# openSX70_WIP_NEW_LAYOUT_20171230_V30_man.net
KiCad netlist of a schematic drawn in EAGLE
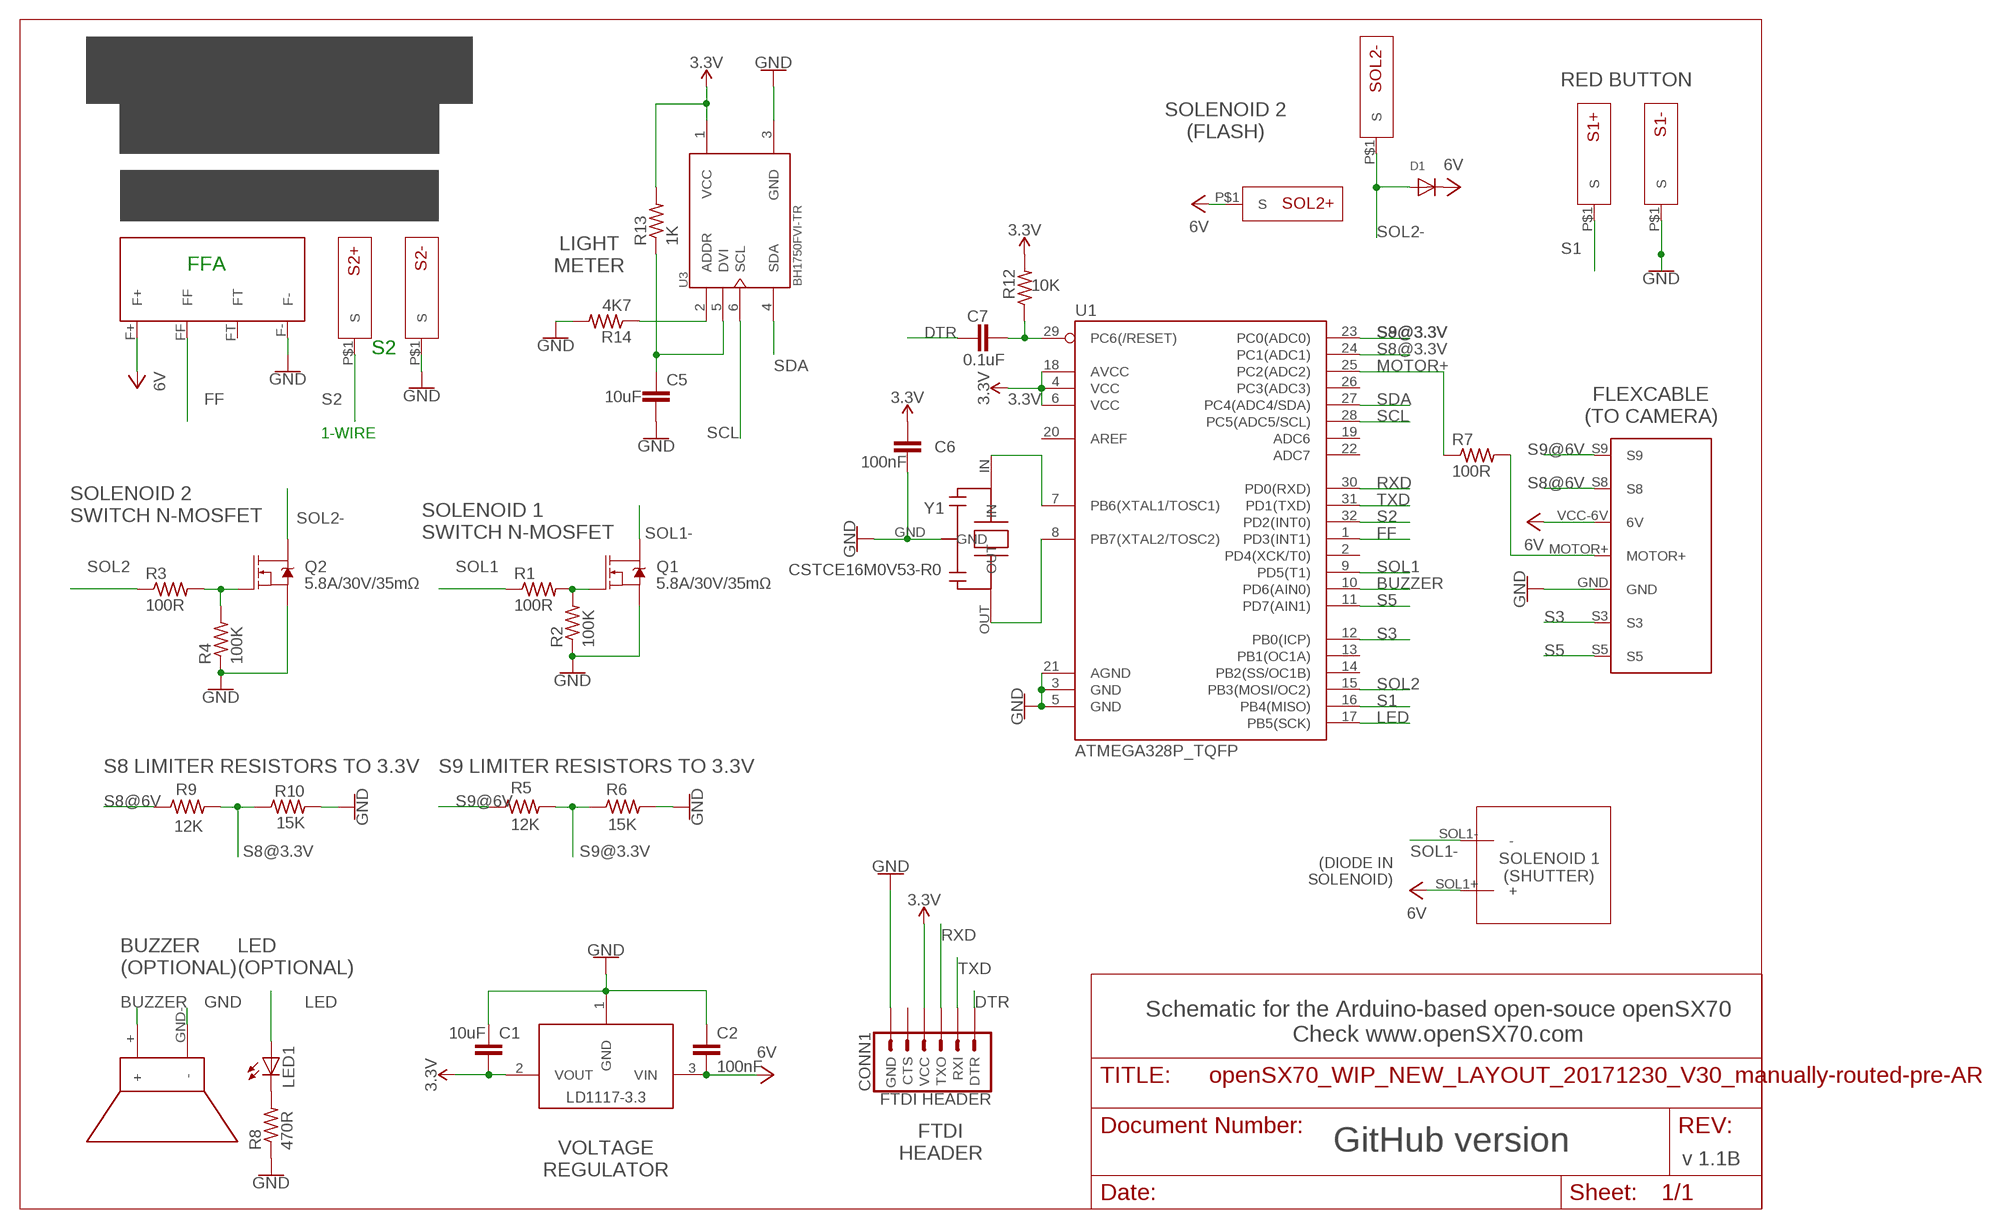
[diagram p0: schematic, sheet 1]

(export (version "E")
  (design (tool "Eeschema 10.0.6"))
  (components
    (comp (ref "BUZZ1")
      (value "CSET8-5G")
      (footprint "eagle-import:CSET8-5G_PACKAGE")
      (libsource (lib "eagle-import") (part "CSET8-5G"))
    )
    (comp (ref "C1")
      (value "10uF")
      (footprint "eagle-import:0603")
      (libsource (lib "eagle-import") (part "10UF-0603-6.3V-20%"))
    )
    (comp (ref "C2")
      (value "100nF")
      (footprint "eagle-import:C0603K")
      (libsource (lib "eagle-import") (part "C-EUC0603K"))
    )
    (comp (ref "C5")
      (value "10uF")
      (footprint "eagle-import:0603")
      (libsource (lib "eagle-import") (part "10UF-0603-6.3V-20%"))
    )
    (comp (ref "C6")
      (value "100nF")
      (footprint "eagle-import:C0805")
      (libsource (lib "eagle-import") (part "resistor_C-EUC0805"))
    )
    (comp (ref "C7")
      (value "0.1uF")
      (footprint "eagle-import:0603")
      (libsource (lib "eagle-import") (part "0.1UF-0603-25V-(+80/-20%)"))
    )
    (comp (ref "CONN1")
      (value "FTDI HEADER")
      (footprint "eagle-import:1X06")
      (libsource (lib "eagle-import") (part "6_PIN_SERIAL_TARGET"))
    )
    (comp (ref "D1")
      (value "DIODESOD-523")
      (footprint "eagle-import:SOD-523")
      (libsource (lib "eagle-import") (part "DIODESOD-523"))
    )
    (comp (ref "LD11173.3V")
      (value "LD1117 3.3V")
      (footprint "eagle-import:SOT223")
      (fields (field (name "MF") "Advanced Monolithic Systems") (field (name "MP") "AMS1117-5.0"))
      (libsource (lib "eagle-import") (part "LD1117-3.3"))
    )
    (comp (ref "LED1")
      (value "LEDCHIPLED_0805")
      (footprint "eagle-import:CHIPLED_0805")
      (libsource (lib "eagle-import") (part "LEDCHIPLED_0805"))
    )
    (comp (ref "Q1")
      (value "5.8A/30V/35mΩ")
      (footprint "eagle-import:SOT23-3")
      (libsource (lib "eagle-import") (part "MOSFET-NCH-AO3404A"))
    )
    (comp (ref "Q2")
      (value "5.8A/30V/35mΩ")
      (footprint "eagle-import:SOT23-3")
      (libsource (lib "eagle-import") (part "MOSFET-NCH-AO3404A"))
    )
    (comp (ref "R1")
      (value "100R")
      (footprint "eagle-import:R0603")
      (libsource (lib "eagle-import") (part "R-US_R0603"))
    )
    (comp (ref "R2")
      (value "100K")
      (footprint "eagle-import:R0603")
      (libsource (lib "eagle-import") (part "R-US_R0603"))
    )
    (comp (ref "R3")
      (value "100R")
      (footprint "eagle-import:R0603")
      (libsource (lib "eagle-import") (part "R-US_R0603"))
    )
    (comp (ref "R4")
      (value "100K")
      (footprint "eagle-import:R0603")
      (libsource (lib "eagle-import") (part "R-US_R0603"))
    )
    (comp (ref "R5")
      (value "12K")
      (footprint "eagle-import:R0603")
      (libsource (lib "eagle-import") (part "R-US_R0603"))
    )
    (comp (ref "R6")
      (value "15K")
      (footprint "eagle-import:R0603")
      (libsource (lib "eagle-import") (part "R-US_R0603"))
    )
    (comp (ref "R7")
      (value "100R")
      (footprint "eagle-import:R0603")
      (libsource (lib "eagle-import") (part "R-US_R0603"))
    )
    (comp (ref "R8")
      (value "470R")
      (footprint "eagle-import:R0603")
      (libsource (lib "eagle-import") (part "R-US_R0603"))
    )
    (comp (ref "R9")
      (value "12K")
      (footprint "eagle-import:R0603")
      (libsource (lib "eagle-import") (part "R-US_R0603"))
    )
    (comp (ref "R10")
      (value "15K")
      (footprint "eagle-import:R0603")
      (libsource (lib "eagle-import") (part "R-US_R0603"))
    )
    (comp (ref "R12")
      (value "10K")
      (footprint "eagle-import:R0603")
      (libsource (lib "eagle-import") (part "R-US_R0603"))
    )
    (comp (ref "R13")
      (value "1K")
      (footprint "eagle-import:R0603")
      (libsource (lib "eagle-import") (part "R-US_R0603"))
    )
    (comp (ref "R14")
      (value "4K7")
      (footprint "eagle-import:R0603")
      (libsource (lib "eagle-import") (part "R-US_R0603"))
    )
    (comp (ref "S1+")
      (value "SX70_S-PAD")
      (footprint "eagle-import:SX70-S-PAD")
      (libsource (lib "eagle-import") (part "SX70_S-PAD"))
    )
    (comp (ref "S1-")
      (value "SX70_S-PAD")
      (footprint "eagle-import:SX70-S-PAD")
      (libsource (lib "eagle-import") (part "SX70_S-PAD"))
    )
    (comp (ref "S2+")
      (value "SX70_S-PAD")
      (footprint "eagle-import:SX70-S-PAD")
      (libsource (lib "eagle-import") (part "SX70_S-PAD"))
    )
    (comp (ref "S2-")
      (value "SX70_S-PAD")
      (footprint "eagle-import:SX70-S-PAD")
      (libsource (lib "eagle-import") (part "SX70_S-PAD"))
    )
    (comp (ref "SOL1")
      (value "SX70-SOLENOID1-2PADS")
      (footprint "eagle-import:SX70-SOLENOID1-2")
      (libsource (lib "eagle-import") (part "SX70-SOLENOID1-2PADS"))
    )
    (comp (ref "SOL2+")
      (value "SX70_S-PAD")
      (footprint "eagle-import:SX70-S-PAD")
      (libsource (lib "eagle-import") (part "SX70_S-PAD"))
    )
    (comp (ref "SOL2-")
      (value "SX70_S-PAD")
      (footprint "eagle-import:SX70-S-PAD")
      (libsource (lib "eagle-import") (part "SX70_S-PAD"))
    )
    (comp (ref "U$1")
      (value "SX70-7-PAD")
      (footprint "eagle-import:SX70-7-PAD")
      (libsource (lib "eagle-import") (part "SX70-7-PAD"))
    )
    (comp (ref "U$2")
      (value "FFA")
      (footprint "eagle-import:FFA-PAD-PACKAGE")
      (libsource (lib "eagle-import") (part "SX70-FFA-PAD"))
    )
    (comp (ref "U1")
      (value "ATMEGA328P_TQFP")
      (footprint "eagle-import:TQFP32-08")
      (libsource (lib "eagle-import") (part "ATMEGA328P_TQFP"))
    )
    (comp (ref "U3")
      (value "BH1750FVI-TR")
      (footprint "eagle-import:SOTFL50P300X75-6N")
      (fields (field (name "MF") "Rohm"))
      (libsource (lib "eagle-import") (part "BH1750FVI-TR"))
    )
    (comp (ref "Y1")
      (value "CSTCE16M0V53-R0")
      (footprint "eagle-import:CFP95P160X100-3N")
      (fields (field (name "MF") "Murata"))
      (libsource (lib "eagle-import") (part "CSTCE16M0V53-R0"))
    )
  )
  (nets
    (net (code "1") (name "/BUZZER") (class "Default")
      (node (ref "BUZZ1") (pin "+") (pinfunction "+_+") (pintype "bidirectional"))
      (node (ref "U1") (pin "10") (pinfunction "PD6(AIN0)_10") (pintype "bidirectional"))
    )
    (net (code "2") (name "/DTR") (class "Default")
      (node (ref "C7") (pin "1") (pinfunction "1_1") (pintype "passive"))
      (node (ref "CONN1") (pin "1") (pinfunction "DTR_1") (pintype "passive"))
    )
    (net (code "3") (name "/FF") (class "Default")
      (node (ref "U$2") (pin "FF") (pinfunction "FF_FF") (pintype "bidirectional"))
      (node (ref "U1") (pin "1") (pinfunction "PD3(INT1)_1") (pintype "bidirectional"))
    )
    (net (code "4") (name "/LED") (class "Default")
      (node (ref "LED1") (pin "A") (pinfunction "A_A") (pintype "passive"))
      (node (ref "U1") (pin "17") (pinfunction "PB5(SCK)_17") (pintype "bidirectional"))
    )
    (net (code "5") (name "/MOTOR+") (class "Default")
      (node (ref "R7") (pin "1") (pinfunction "1_1") (pintype "passive"))
      (node (ref "U1") (pin "25") (pinfunction "PC2(ADC2)_25") (pintype "bidirectional"))
    )
    (net (code "6") (name "/RXD") (class "Default")
      (node (ref "CONN1") (pin "3") (pinfunction "TXO_3") (pintype "passive"))
      (node (ref "U1") (pin "30") (pinfunction "PD0(RXD)_30") (pintype "bidirectional"))
    )
    (net (code "7") (name "/S1") (class "Default")
      (node (ref "S1+") (pin "P$1") (pinfunction "S_P$1") (pintype "bidirectional"))
      (node (ref "U1") (pin "16") (pinfunction "PB4(MISO)_16") (pintype "bidirectional"))
    )
    (net (code "8") (name "/S2") (class "Default")
      (node (ref "S2+") (pin "P$1") (pinfunction "S_P$1") (pintype "bidirectional"))
      (node (ref "U1") (pin "32") (pinfunction "PD2(INT0)_32") (pintype "bidirectional"))
    )
    (net (code "9") (name "/S3") (class "Default")
      (node (ref "U$1") (pin "S3") (pinfunction "S3_S3") (pintype "bidirectional"))
      (node (ref "U1") (pin "12") (pinfunction "PB0(ICP)_12") (pintype "bidirectional"))
    )
    (net (code "10") (name "/S5") (class "Default")
      (node (ref "U$1") (pin "S5") (pinfunction "S5_S5") (pintype "bidirectional"))
      (node (ref "U1") (pin "11") (pinfunction "PD7(AIN1)_11") (pintype "bidirectional"))
    )
    (net (code "11") (name "/S8@3.3V") (class "Default")
      (node (ref "R10") (pin "1") (pinfunction "1_1") (pintype "passive"))
      (node (ref "R9") (pin "2") (pinfunction "2_2") (pintype "passive"))
      (node (ref "U1") (pin "24") (pinfunction "PC1(ADC1)_24") (pintype "bidirectional"))
    )
    (net (code "12") (name "/S8@6V") (class "Default")
      (node (ref "R9") (pin "1") (pinfunction "1_1") (pintype "passive"))
      (node (ref "U$1") (pin "S8") (pinfunction "S8_S8") (pintype "bidirectional"))
    )
    (net (code "13") (name "/S9@3.3V") (class "Default")
      (node (ref "R5") (pin "2") (pinfunction "2_2") (pintype "passive"))
      (node (ref "R6") (pin "1") (pinfunction "1_1") (pintype "passive"))
      (node (ref "U1") (pin "23") (pinfunction "PC0(ADC0)_23") (pintype "bidirectional"))
    )
    (net (code "14") (name "/S9@6V") (class "Default")
      (node (ref "R5") (pin "1") (pinfunction "1_1") (pintype "passive"))
      (node (ref "U$1") (pin "S9") (pinfunction "S9_S9") (pintype "bidirectional"))
    )
    (net (code "15") (name "/SCL") (class "Default")
      (node (ref "U1") (pin "28") (pinfunction "PC5(ADC5/SCL)_28") (pintype "bidirectional"))
      (node (ref "U3") (pin "6") (pinfunction "SCL_6") (pintype "input"))
    )
    (net (code "16") (name "/SDA") (class "Default")
      (node (ref "U1") (pin "27") (pinfunction "PC4(ADC4/SDA)_27") (pintype "bidirectional"))
      (node (ref "U3") (pin "4") (pinfunction "SDA_4") (pintype "bidirectional"))
    )
    (net (code "17") (name "/SOL1") (class "Default")
      (node (ref "R1") (pin "1") (pinfunction "1_1") (pintype "passive"))
      (node (ref "U1") (pin "9") (pinfunction "PD5(T1)_9") (pintype "bidirectional"))
    )
    (net (code "18") (name "/SOL1-") (class "Default")
      (node (ref "Q1") (pin "3") (pinfunction "D_3") (pintype "bidirectional"))
      (node (ref "SOL1") (pin "SOL1-") (pinfunction "-_SOL1-") (pintype "bidirectional"))
    )
    (net (code "19") (name "/SOL2") (class "Default")
      (node (ref "R3") (pin "1") (pinfunction "1_1") (pintype "passive"))
      (node (ref "U1") (pin "15") (pinfunction "PB3(MOSI/OC2)_15") (pintype "bidirectional"))
    )
    (net (code "20") (name "/SOL2-") (class "Default")
      (node (ref "D1") (pin "A") (pinfunction "A_A") (pintype "passive"))
      (node (ref "Q2") (pin "3") (pinfunction "D_3") (pintype "bidirectional"))
      (node (ref "SOL2-") (pin "P$1") (pinfunction "S_P$1") (pintype "bidirectional"))
    )
    (net (code "21") (name "/TXD") (class "Default")
      (node (ref "CONN1") (pin "2") (pinfunction "RXI_2") (pintype "passive"))
      (node (ref "U1") (pin "31") (pinfunction "PD1(TXD)_31") (pintype "bidirectional"))
    )
    (net (code "22") (name "3.3V") (class "Default")
      (node (ref "C1") (pin "2") (pinfunction "2_2") (pintype "passive"))
      (node (ref "C6") (pin "1") (pinfunction "1_1") (pintype "passive"))
      (node (ref "CONN1") (pin "4") (pinfunction "VCC_4") (pintype "passive"))
      (node (ref "LD11173.3V") (pin "2") (pinfunction "VOUT_2") (pintype "bidirectional"))
      (node (ref "R12") (pin "2") (pinfunction "2_2") (pintype "passive"))
      (node (ref "R13") (pin "2") (pinfunction "2_2") (pintype "passive"))
      (node (ref "U1") (pin "18") (pinfunction "AVCC_18") (pintype "bidirectional"))
      (node (ref "U1") (pin "4") (pinfunction "VCC_4") (pintype "bidirectional"))
      (node (ref "U1") (pin "6") (pinfunction "VCC_6") (pintype "bidirectional"))
      (node (ref "U3") (pin "1") (pinfunction "VCC_1") (pintype "power_in"))
    )
    (net (code "23") (name "6V") (class "Default")
      (node (ref "C2") (pin "2") (pinfunction "2_2") (pintype "passive"))
      (node (ref "D1") (pin "K") (pinfunction "C_K") (pintype "passive"))
      (node (ref "LD11173.3V") (pin "3") (pinfunction "VIN_3") (pintype "bidirectional"))
      (node (ref "SOL1") (pin "SOL1+") (pinfunction "+_SOL1+") (pintype "bidirectional"))
      (node (ref "SOL2+") (pin "P$1") (pinfunction "S_P$1") (pintype "bidirectional"))
      (node (ref "U$1") (pin "VCC-6V") (pinfunction "6V_VCC-6V") (pintype "bidirectional"))
      (node (ref "U$2") (pin "F+") (pinfunction "F+_F+") (pintype "bidirectional"))
    )
    (net (code "24") (name "GND") (class "Default")
      (node (ref "BUZZ1") (pin "GND-") (pinfunction "-_GND-") (pintype "bidirectional"))
      (node (ref "C1") (pin "1") (pinfunction "1_1") (pintype "passive"))
      (node (ref "C2") (pin "1") (pinfunction "1_1") (pintype "passive"))
      (node (ref "C5") (pin "2") (pinfunction "2_2") (pintype "passive"))
      (node (ref "C6") (pin "2") (pinfunction "2_2") (pintype "passive"))
      (node (ref "CONN1") (pin "6") (pinfunction "GND_6") (pintype "passive"))
      (node (ref "LD11173.3V") (pin "1") (pinfunction "GND_1") (pintype "bidirectional"))
      (node (ref "Q1") (pin "2") (pinfunction "S_2") (pintype "bidirectional"))
      (node (ref "Q2") (pin "2") (pinfunction "S_2") (pintype "bidirectional"))
      (node (ref "R10") (pin "2") (pinfunction "2_2") (pintype "passive"))
      (node (ref "R14") (pin "2") (pinfunction "2_2") (pintype "passive"))
      (node (ref "R2") (pin "1") (pinfunction "1_1") (pintype "passive"))
      (node (ref "R4") (pin "1") (pinfunction "1_1") (pintype "passive"))
      (node (ref "R6") (pin "2") (pinfunction "2_2") (pintype "passive"))
      (node (ref "R8") (pin "1") (pinfunction "1_1") (pintype "passive"))
      (node (ref "S1-") (pin "P$1") (pinfunction "S_P$1") (pintype "bidirectional"))
      (node (ref "S2-") (pin "P$1") (pinfunction "S_P$1") (pintype "bidirectional"))
      (node (ref "U$1") (pin "GND") (pinfunction "GND_GND") (pintype "bidirectional"))
      (node (ref "U$2") (pin "F-") (pinfunction "F-_F-") (pintype "bidirectional"))
      (node (ref "U1") (pin "21") (pinfunction "AGND_21") (pintype "bidirectional"))
      (node (ref "U1") (pin "3") (pinfunction "GND_3") (pintype "bidirectional"))
      (node (ref "U1") (pin "5") (pinfunction "GND_5") (pintype "bidirectional"))
      (node (ref "U3") (pin "3") (pinfunction "GND_3") (pintype "power_in"))
      (node (ref "Y1") (pin "GND") (pinfunction "GND_GND") (pintype "passive"))
    )
    (net (code "25") (name "Net-(LED1-PadC)") (class "Default")
      (node (ref "LED1") (pin "C") (pinfunction "C_C") (pintype "passive"))
      (node (ref "R8") (pin "2") (pinfunction "2_2") (pintype "passive"))
    )
    (net (code "26") (name "Net-(Q1-G)") (class "Default")
      (node (ref "Q1") (pin "1") (pinfunction "G_1") (pintype "bidirectional"))
      (node (ref "R1") (pin "2") (pinfunction "2_2") (pintype "passive"))
      (node (ref "R2") (pin "2") (pinfunction "2_2") (pintype "passive"))
    )
    (net (code "27") (name "Net-(Q2-G)") (class "Default")
      (node (ref "Q2") (pin "1") (pinfunction "G_1") (pintype "bidirectional"))
      (node (ref "R3") (pin "2") (pinfunction "2_2") (pintype "passive"))
      (node (ref "R4") (pin "2") (pinfunction "2_2") (pintype "passive"))
    )
    (net (code "28") (name "Net-(R7-Pad2)") (class "Default")
      (node (ref "R7") (pin "2") (pinfunction "2_2") (pintype "passive"))
      (node (ref "U$1") (pin "MOTOR+") (pinfunction "MOTOR+_MOTOR+") (pintype "bidirectional"))
    )
    (net (code "29") (name "Net-(U1-PB6(XTAL1{slash}TOSC1))") (class "Default")
      (node (ref "U1") (pin "7") (pinfunction "PB6(XTAL1/TOSC1)_7") (pintype "bidirectional"))
      (node (ref "Y1") (pin "IN") (pinfunction "IN_IN") (pintype "input"))
    )
    (net (code "30") (name "Net-(U1-PB7(XTAL2{slash}TOSC2))") (class "Default")
      (node (ref "U1") (pin "8") (pinfunction "PB7(XTAL2/TOSC2)_8") (pintype "bidirectional"))
      (node (ref "Y1") (pin "OUT") (pinfunction "OUT_OUT") (pintype "output"))
    )
    (net (code "31") (name "Net-(U1-PC6({slash}RESET))") (class "Default")
      (node (ref "C7") (pin "2") (pinfunction "2_2") (pintype "passive"))
      (node (ref "R12") (pin "1") (pinfunction "1_1") (pintype "passive"))
      (node (ref "U1") (pin "29") (pinfunction "PC6(/RESET)_29") (pintype "bidirectional"))
    )
    (net (code "32") (name "Net-(U3-ADDR)") (class "Default")
      (node (ref "R14") (pin "1") (pinfunction "1_1") (pintype "passive"))
      (node (ref "U3") (pin "2") (pinfunction "ADDR_2") (pintype "input"))
    )
    (net (code "33") (name "Net-(U3-DVI)") (class "Default")
      (node (ref "C5") (pin "1") (pinfunction "1_1") (pintype "passive"))
      (node (ref "R13") (pin "1") (pinfunction "1_1") (pintype "passive"))
      (node (ref "U3") (pin "5") (pinfunction "DVI_5") (pintype "input"))
    )
    (net (code "34") (name "unconnected-(CONN1-CTS-Pad5)") (class "Default")
      (node (ref "CONN1") (pin "5") (pinfunction "CTS_5") (pintype "passive"))
    )
    (net (code "35") (name "unconnected-(U$2-PadFT)") (class "Default")
      (node (ref "U$2") (pin "FT") (pinfunction "FT_FT") (pintype "bidirectional"))
    )
    (net (code "36") (name "unconnected-(U1-ADC6-Pad19)") (class "Default")
      (node (ref "U1") (pin "19") (pinfunction "ADC6_19") (pintype "bidirectional"))
    )
    (net (code "37") (name "unconnected-(U1-ADC7-Pad22)") (class "Default")
      (node (ref "U1") (pin "22") (pinfunction "ADC7_22") (pintype "bidirectional"))
    )
    (net (code "38") (name "unconnected-(U1-AREF-Pad20)") (class "Default")
      (node (ref "U1") (pin "20") (pinfunction "AREF_20") (pintype "bidirectional"))
    )
    (net (code "39") (name "unconnected-(U1-PB1(OC1A)-Pad13)") (class "Default")
      (node (ref "U1") (pin "13") (pinfunction "PB1(OC1A)_13") (pintype "bidirectional"))
    )
    (net (code "40") (name "unconnected-(U1-PB2(SS{slash}OC1B)-Pad14)") (class "Default")
      (node (ref "U1") (pin "14") (pinfunction "PB2(SS/OC1B)_14") (pintype "bidirectional"))
    )
    (net (code "41") (name "unconnected-(U1-PC3(ADC3)-Pad26)") (class "Default")
      (node (ref "U1") (pin "26") (pinfunction "PC3(ADC3)_26") (pintype "bidirectional"))
    )
    (net (code "42") (name "unconnected-(U1-PD4(XCK{slash}T0)-Pad2)") (class "Default")
      (node (ref "U1") (pin "2") (pinfunction "PD4(XCK/T0)_2") (pintype "bidirectional"))
    )
  )
)
